# BalEv_AINb_v1_0.net
KiCad netlist of a schematic drawn in Altium Designer
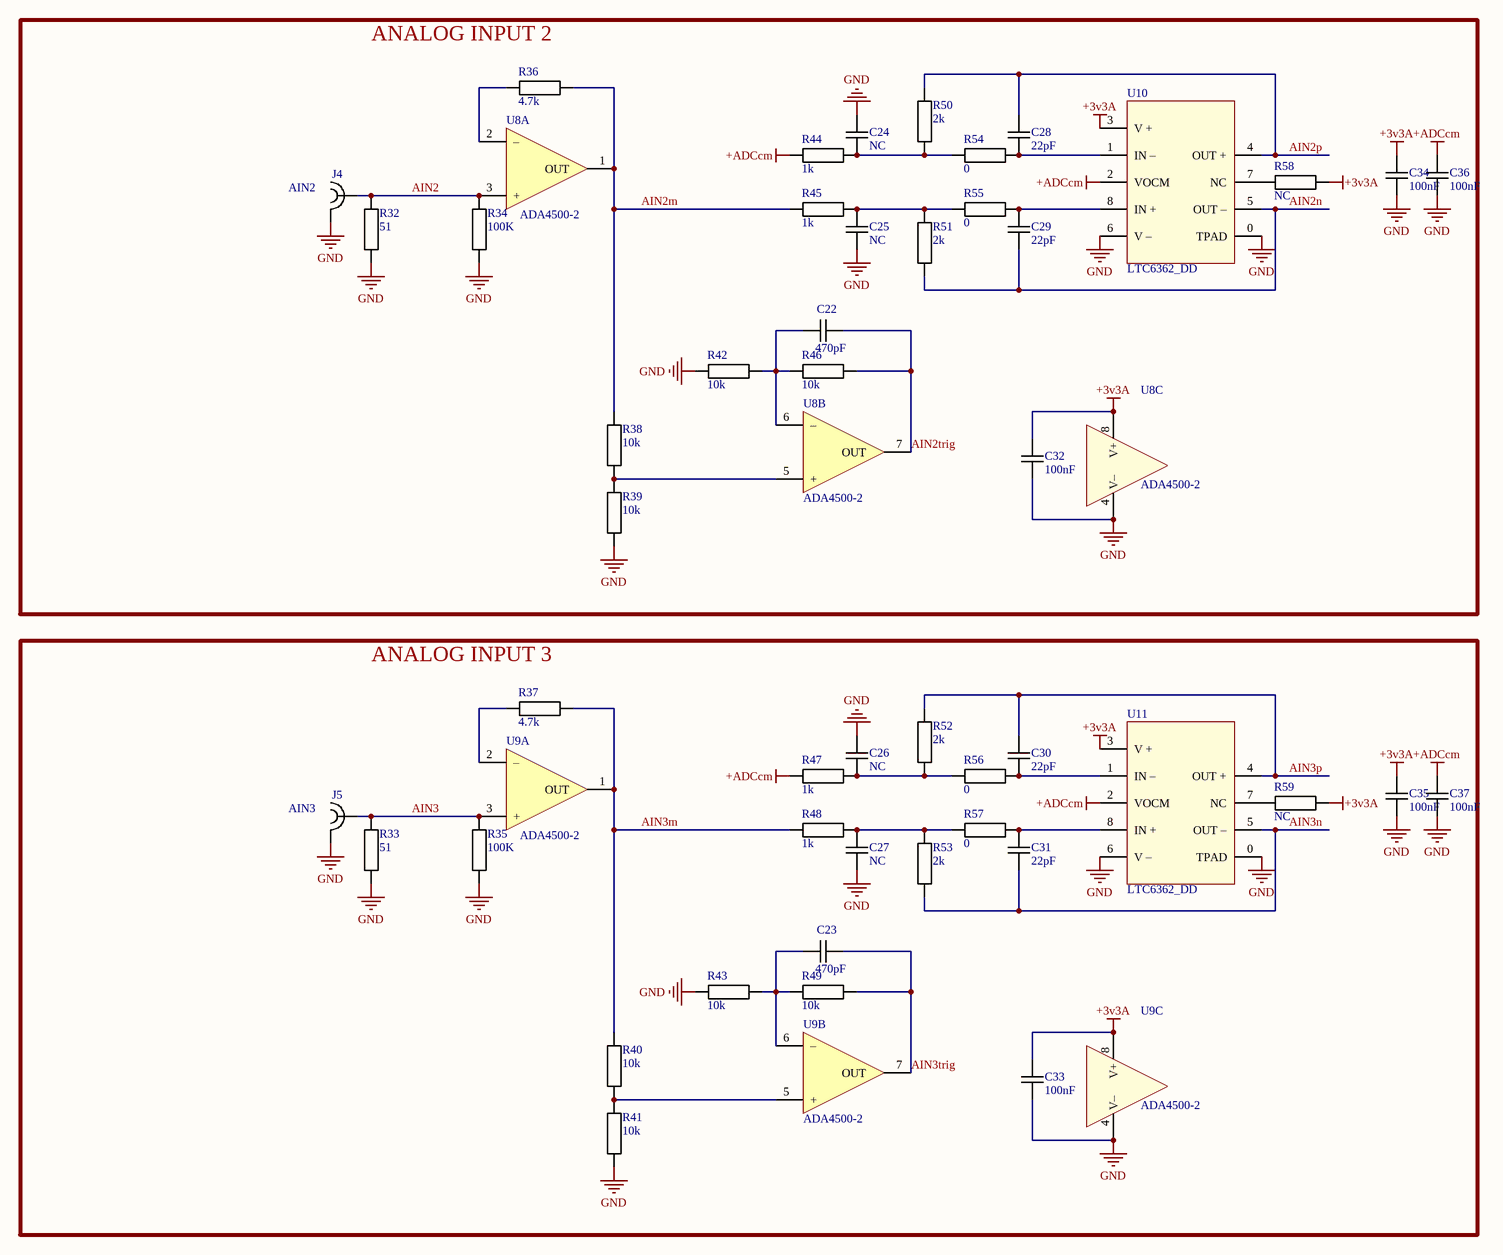
[diagram p0: BalEv_AINb_v1_0.SchDoc]

(export (version "E")
  (design (tool "Eeschema 10.0.6"))
  (components
    (comp (ref "C22")
      (value "470pF")
      (footprint "CAPACITOR 1005 REFLOW")
      (description "Capacitor")
      (libsource (lib "Capacitor") (part "Capacitor"))
    )
    (comp (ref "C23")
      (value "470pF")
      (footprint "CAPACITOR 1005 REFLOW")
      (description "Capacitor")
      (libsource (lib "Capacitor") (part "Capacitor"))
    )
    (comp (ref "C24")
      (value "NC")
      (footprint "CAPACITOR 1005 REFLOW")
      (description "Capacitor")
      (libsource (lib "Capacitor") (part "Capacitor"))
    )
    (comp (ref "C25")
      (value "NC")
      (footprint "CAPACITOR 1005 REFLOW")
      (description "Capacitor")
      (libsource (lib "Capacitor") (part "Capacitor"))
    )
    (comp (ref "C26")
      (value "NC")
      (footprint "CAPACITOR 1005 REFLOW")
      (description "Capacitor")
      (libsource (lib "Capacitor") (part "Capacitor"))
    )
    (comp (ref "C27")
      (value "NC")
      (footprint "CAPACITOR 1005 REFLOW")
      (description "Capacitor")
      (libsource (lib "Capacitor") (part "Capacitor"))
    )
    (comp (ref "C28")
      (value "22pF")
      (footprint "CAPACITOR 1005 REFLOW")
      (description "Capacitor")
      (libsource (lib "Capacitor") (part "Capacitor"))
    )
    (comp (ref "C29")
      (value "22pF")
      (footprint "CAPACITOR 1005 REFLOW")
      (description "Capacitor")
      (libsource (lib "Capacitor") (part "Capacitor"))
    )
    (comp (ref "C30")
      (value "22pF")
      (footprint "CAPACITOR 1005 REFLOW")
      (description "Capacitor")
      (libsource (lib "Capacitor") (part "Capacitor"))
    )
    (comp (ref "C31")
      (value "22pF")
      (footprint "CAPACITOR 1005 REFLOW")
      (description "Capacitor")
      (libsource (lib "Capacitor") (part "Capacitor"))
    )
    (comp (ref "C32")
      (value "100nF")
      (footprint "CAPACITOR 1005 REFLOW")
      (description "Capacitor")
      (libsource (lib "Capacitor") (part "Capacitor"))
    )
    (comp (ref "C33")
      (value "100nF")
      (footprint "CAPACITOR 1005 REFLOW")
      (description "Capacitor")
      (libsource (lib "Capacitor") (part "Capacitor"))
    )
    (comp (ref "C34")
      (value "100nF")
      (footprint "CAPACITOR 1005 REFLOW")
      (description "Capacitor")
      (libsource (lib "Capacitor") (part "Capacitor"))
    )
    (comp (ref "C35")
      (value "100nF")
      (footprint "CAPACITOR 1005 REFLOW")
      (description "Capacitor")
      (libsource (lib "Capacitor") (part "Capacitor"))
    )
    (comp (ref "C36")
      (value "100nF")
      (footprint "CAPACITOR 1005 REFLOW")
      (description "Capacitor")
      (libsource (lib "Capacitor") (part "Capacitor"))
    )
    (comp (ref "C37")
      (value "100nF")
      (footprint "CAPACITOR 1005 REFLOW")
      (description "Capacitor")
      (libsource (lib "Capacitor") (part "Capacitor"))
    )
    (comp (ref "J4")
      (value "AIN2")
      (footprint "SMA EDGE Molex 732511150")
      (description "SMA EDGE Molex 732511150")
      (libsource (lib "Connector") (part "SMA EDGE Molex 732511150"))
    )
    (comp (ref "J5")
      (value "AIN3")
      (footprint "SMA EDGE Molex 732511150")
      (description "SMA EDGE Molex 732511150")
      (libsource (lib "Connector") (part "SMA EDGE Molex 732511150"))
    )
    (comp (ref "R32")
      (value "51")
      (footprint "RESISTOR 1005 REFLOW")
      (description "Resistor")
      (libsource (lib "Resistor") (part "Resistor"))
    )
    (comp (ref "R33")
      (value "51")
      (footprint "RESISTOR 1005 REFLOW")
      (description "Resistor")
      (libsource (lib "Resistor") (part "Resistor"))
    )
    (comp (ref "R34")
      (value "100K")
      (footprint "RESISTOR 1005 REFLOW")
      (description "Resistor")
      (libsource (lib "Resistor") (part "Resistor"))
    )
    (comp (ref "R35")
      (value "100K")
      (footprint "RESISTOR 1005 REFLOW")
      (description "Resistor")
      (libsource (lib "Resistor") (part "Resistor"))
    )
    (comp (ref "R36")
      (value "4.7k")
      (footprint "RESISTOR 1005 REFLOW")
      (description "Resistor")
      (libsource (lib "Resistor") (part "Resistor"))
    )
    (comp (ref "R37")
      (value "4.7k")
      (footprint "RESISTOR 1005 REFLOW")
      (description "Resistor")
      (libsource (lib "Resistor") (part "Resistor"))
    )
    (comp (ref "R38")
      (value "10k")
      (footprint "RESISTOR 1005 REFLOW")
      (description "Resistor")
      (libsource (lib "Resistor") (part "Resistor"))
    )
    (comp (ref "R39")
      (value "10k")
      (footprint "RESISTOR 1005 REFLOW")
      (description "Resistor")
      (libsource (lib "Resistor") (part "Resistor"))
    )
    (comp (ref "R40")
      (value "10k")
      (footprint "RESISTOR 1005 REFLOW")
      (description "Resistor")
      (libsource (lib "Resistor") (part "Resistor"))
    )
    (comp (ref "R41")
      (value "10k")
      (footprint "RESISTOR 1005 REFLOW")
      (description "Resistor")
      (libsource (lib "Resistor") (part "Resistor"))
    )
    (comp (ref "R42")
      (value "10k")
      (footprint "RESISTOR 1005 REFLOW")
      (description "Resistor")
      (libsource (lib "Resistor") (part "Resistor"))
    )
    (comp (ref "R43")
      (value "10k")
      (footprint "RESISTOR 1005 REFLOW")
      (description "Resistor")
      (libsource (lib "Resistor") (part "Resistor"))
    )
    (comp (ref "R44")
      (value "1k")
      (footprint "RESISTOR 1005 REFLOW")
      (description "Resistor")
      (libsource (lib "Resistor") (part "Resistor"))
    )
    (comp (ref "R45")
      (value "1k")
      (footprint "RESISTOR 1005 REFLOW")
      (description "Resistor")
      (libsource (lib "Resistor") (part "Resistor"))
    )
    (comp (ref "R46")
      (value "10k")
      (footprint "RESISTOR 1005 REFLOW")
      (description "Resistor")
      (libsource (lib "Resistor") (part "Resistor"))
    )
    (comp (ref "R47")
      (value "1k")
      (footprint "RESISTOR 1005 REFLOW")
      (description "Resistor")
      (libsource (lib "Resistor") (part "Resistor"))
    )
    (comp (ref "R48")
      (value "1k")
      (footprint "RESISTOR 1005 REFLOW")
      (description "Resistor")
      (libsource (lib "Resistor") (part "Resistor"))
    )
    (comp (ref "R49")
      (value "10k")
      (footprint "RESISTOR 1005 REFLOW")
      (description "Resistor")
      (libsource (lib "Resistor") (part "Resistor"))
    )
    (comp (ref "R50")
      (value "2k")
      (footprint "RESISTOR 1005 REFLOW")
      (description "Resistor")
      (libsource (lib "Resistor") (part "Resistor"))
    )
    (comp (ref "R51")
      (value "2k")
      (footprint "RESISTOR 1005 REFLOW")
      (description "Resistor")
      (libsource (lib "Resistor") (part "Resistor"))
    )
    (comp (ref "R52")
      (value "2k")
      (footprint "RESISTOR 1005 REFLOW")
      (description "Resistor")
      (libsource (lib "Resistor") (part "Resistor"))
    )
    (comp (ref "R53")
      (value "2k")
      (footprint "RESISTOR 1005 REFLOW")
      (description "Resistor")
      (libsource (lib "Resistor") (part "Resistor"))
    )
    (comp (ref "R54")
      (value "0")
      (footprint "RESISTOR 1005 REFLOW")
      (description "Resistor")
      (libsource (lib "Resistor") (part "Resistor"))
    )
    (comp (ref "R55")
      (value "0")
      (footprint "RESISTOR 1005 REFLOW")
      (description "Resistor")
      (libsource (lib "Resistor") (part "Resistor"))
    )
    (comp (ref "R56")
      (value "0")
      (footprint "RESISTOR 1005 REFLOW")
      (description "Resistor")
      (libsource (lib "Resistor") (part "Resistor"))
    )
    (comp (ref "R57")
      (value "0")
      (footprint "RESISTOR 1005 REFLOW")
      (description "Resistor")
      (libsource (lib "Resistor") (part "Resistor"))
    )
    (comp (ref "R58")
      (value "NC")
      (footprint "RESISTOR 1005 REFLOW")
      (description "Resistor")
      (libsource (lib "Resistor") (part "Resistor"))
    )
    (comp (ref "R59")
      (value "NC")
      (footprint "RESISTOR 1005 REFLOW")
      (description "Resistor")
      (libsource (lib "Resistor") (part "Resistor"))
    )
    (comp (ref "U8")
      (value "ADA4500-2")
      (footprint "MSOP8 P0.65 C3.0X3.0 H1.1")
      (description "Generic dual OPA 8 pins")
      (libsource (lib "Amplifier") (part "OPA DUAL"))
    )
    (comp (ref "U9")
      (value "ADA4500-2")
      (footprint "MSOP8 P0.65 C3.0X3.0 H1.1")
      (description "Generic dual OPA 8 pins")
      (libsource (lib "Amplifier") (part "OPA DUAL"))
    )
    (comp (ref "U10")
      (value "LTC6362_DD")
      (footprint "LFCSP8 P0.5 C3.0x2.8 H1.0")
      (description "IC OPAMP DIFF 410MHZ RRO 8LFCSP")
      (libsource (lib "Amplifier") (part "AD8139ACP"))
    )
    (comp (ref "U11")
      (value "LTC6362_DD")
      (footprint "LFCSP8 P0.5 C3.0x2.8 H1.0")
      (description "IC OPAMP DIFF 410MHZ RRO 8LFCSP")
      (libsource (lib "Amplifier") (part "AD8139ACP"))
    )
  )
  (nets
    (net (code "1") (name "+3v3A") (class "Default")
      (node (ref "C32") (pin "1") (pinfunction "1_1") (pintype "passive"))
      (node (ref "C33") (pin "1") (pinfunction "1_1") (pintype "passive"))
      (node (ref "C34") (pin "2") (pinfunction "2_2") (pintype "passive"))
      (node (ref "C35") (pin "2") (pinfunction "2_2") (pintype "passive"))
      (node (ref "R58") (pin "2") (pinfunction "2_2") (pintype "passive"))
      (node (ref "R59") (pin "2") (pinfunction "2_2") (pintype "passive"))
      (node (ref "U10") (pin "3") (pinfunction "V_+_3") (pintype "passive"))
      (node (ref "U11") (pin "3") (pinfunction "V_+_3") (pintype "passive"))
      (node (ref "U8") (pin "8") (pinfunction "V+_8") (pintype "passive"))
      (node (ref "U9") (pin "8") (pinfunction "V+_8") (pintype "passive"))
    )
    (net (code "2") (name "+ADCcm") (class "Default")
      (node (ref "C36") (pin "2") (pinfunction "2_2") (pintype "passive"))
      (node (ref "C37") (pin "2") (pinfunction "2_2") (pintype "passive"))
      (node (ref "R44") (pin "1") (pinfunction "1_1") (pintype "passive"))
      (node (ref "R47") (pin "1") (pinfunction "1_1") (pintype "passive"))
      (node (ref "U10") (pin "2") (pinfunction "VOCM_2") (pintype "passive"))
      (node (ref "U11") (pin "2") (pinfunction "VOCM_2") (pintype "passive"))
    )
    (net (code "3") (name "/AIN2") (class "Default")
      (node (ref "J4") (pin "1") (pinfunction "1_1") (pintype "passive"))
      (node (ref "R32") (pin "2") (pinfunction "2_2") (pintype "passive"))
      (node (ref "R34") (pin "2") (pinfunction "2_2") (pintype "passive"))
      (node (ref "U8") (pin "3") (pinfunction "+_3") (pintype "passive"))
    )
    (net (code "4") (name "/AIN2m") (class "Default")
      (node (ref "R36") (pin "2") (pinfunction "2_2") (pintype "passive"))
      (node (ref "R38") (pin "1") (pinfunction "1_1") (pintype "passive"))
      (node (ref "R45") (pin "1") (pinfunction "1_1") (pintype "passive"))
      (node (ref "U8") (pin "1") (pinfunction "OUT_1") (pintype "passive"))
    )
    (net (code "5") (name "/AIN2n") (class "Default")
      (node (ref "C29") (pin "1") (pinfunction "1_1") (pintype "passive"))
      (node (ref "R51") (pin "2") (pinfunction "2_2") (pintype "passive"))
      (node (ref "U10") (pin "5") (pinfunction "OUT_–_5") (pintype "passive"))
    )
    (net (code "6") (name "/AIN2p") (class "Default")
      (node (ref "C28") (pin "1") (pinfunction "1_1") (pintype "passive"))
      (node (ref "R50") (pin "2") (pinfunction "2_2") (pintype "passive"))
      (node (ref "U10") (pin "4") (pinfunction "OUT_+_4") (pintype "passive"))
    )
    (net (code "7") (name "/AIN2trig") (class "Default")
      (node (ref "C22") (pin "1") (pinfunction "1_1") (pintype "passive"))
      (node (ref "R46") (pin "2") (pinfunction "2_2") (pintype "passive"))
      (node (ref "U8") (pin "7") (pinfunction "OUT_7") (pintype "passive"))
    )
    (net (code "8") (name "/AIN3") (class "Default")
      (node (ref "J5") (pin "1") (pinfunction "1_1") (pintype "passive"))
      (node (ref "R33") (pin "2") (pinfunction "2_2") (pintype "passive"))
      (node (ref "R35") (pin "2") (pinfunction "2_2") (pintype "passive"))
      (node (ref "U9") (pin "3") (pinfunction "+_3") (pintype "passive"))
    )
    (net (code "9") (name "/AIN3m") (class "Default")
      (node (ref "R37") (pin "2") (pinfunction "2_2") (pintype "passive"))
      (node (ref "R40") (pin "1") (pinfunction "1_1") (pintype "passive"))
      (node (ref "R48") (pin "1") (pinfunction "1_1") (pintype "passive"))
      (node (ref "U9") (pin "1") (pinfunction "OUT_1") (pintype "passive"))
    )
    (net (code "10") (name "/AIN3n") (class "Default")
      (node (ref "C31") (pin "1") (pinfunction "1_1") (pintype "passive"))
      (node (ref "R53") (pin "2") (pinfunction "2_2") (pintype "passive"))
      (node (ref "U11") (pin "5") (pinfunction "OUT_–_5") (pintype "passive"))
    )
    (net (code "11") (name "/AIN3p") (class "Default")
      (node (ref "C30") (pin "1") (pinfunction "1_1") (pintype "passive"))
      (node (ref "R52") (pin "2") (pinfunction "2_2") (pintype "passive"))
      (node (ref "U11") (pin "4") (pinfunction "OUT_+_4") (pintype "passive"))
    )
    (net (code "12") (name "/AIN3trig") (class "Default")
      (node (ref "C23") (pin "1") (pinfunction "1_1") (pintype "passive"))
      (node (ref "R49") (pin "2") (pinfunction "2_2") (pintype "passive"))
      (node (ref "U9") (pin "7") (pinfunction "OUT_7") (pintype "passive"))
    )
    (net (code "13") (name "GND") (class "Default")
      (node (ref "C24") (pin "1") (pinfunction "1_1") (pintype "passive"))
      (node (ref "C25") (pin "2") (pinfunction "2_2") (pintype "passive"))
      (node (ref "C26") (pin "1") (pinfunction "1_1") (pintype "passive"))
      (node (ref "C27") (pin "2") (pinfunction "2_2") (pintype "passive"))
      (node (ref "C32") (pin "2") (pinfunction "2_2") (pintype "passive"))
      (node (ref "C33") (pin "2") (pinfunction "2_2") (pintype "passive"))
      (node (ref "C34") (pin "1") (pinfunction "1_1") (pintype "passive"))
      (node (ref "C35") (pin "1") (pinfunction "1_1") (pintype "passive"))
      (node (ref "C36") (pin "1") (pinfunction "1_1") (pintype "passive"))
      (node (ref "C37") (pin "1") (pinfunction "1_1") (pintype "passive"))
      (node (ref "J4") (pin "2") (pinfunction "2_2") (pintype "passive"))
      (node (ref "J5") (pin "2") (pinfunction "2_2") (pintype "passive"))
      (node (ref "R32") (pin "1") (pinfunction "1_1") (pintype "passive"))
      (node (ref "R33") (pin "1") (pinfunction "1_1") (pintype "passive"))
      (node (ref "R34") (pin "1") (pinfunction "1_1") (pintype "passive"))
      (node (ref "R35") (pin "1") (pinfunction "1_1") (pintype "passive"))
      (node (ref "R39") (pin "2") (pinfunction "2_2") (pintype "passive"))
      (node (ref "R41") (pin "2") (pinfunction "2_2") (pintype "passive"))
      (node (ref "R42") (pin "1") (pinfunction "1_1") (pintype "passive"))
      (node (ref "R43") (pin "1") (pinfunction "1_1") (pintype "passive"))
      (node (ref "U10") (pin "0") (pinfunction "TPAD_0") (pintype "passive"))
      (node (ref "U10") (pin "6") (pinfunction "V_–_6") (pintype "passive"))
      (node (ref "U11") (pin "0") (pinfunction "TPAD_0") (pintype "passive"))
      (node (ref "U11") (pin "6") (pinfunction "V_–_6") (pintype "passive"))
      (node (ref "U8") (pin "4") (pinfunction "V–_4") (pintype "passive"))
      (node (ref "U9") (pin "4") (pinfunction "V–_4") (pintype "passive"))
    )
    (net (code "14") (name "Net-(C24-Pad2)") (class "Default")
      (node (ref "C24") (pin "2") (pinfunction "2_2") (pintype "passive"))
      (node (ref "R44") (pin "2") (pinfunction "2_2") (pintype "passive"))
      (node (ref "R50") (pin "1") (pinfunction "1_1") (pintype "passive"))
      (node (ref "R54") (pin "2") (pinfunction "2_2") (pintype "passive"))
    )
    (net (code "15") (name "Net-(C25-Pad1)") (class "Default")
      (node (ref "C25") (pin "1") (pinfunction "1_1") (pintype "passive"))
      (node (ref "R45") (pin "2") (pinfunction "2_2") (pintype "passive"))
      (node (ref "R51") (pin "1") (pinfunction "1_1") (pintype "passive"))
      (node (ref "R55") (pin "1") (pinfunction "1_1") (pintype "passive"))
    )
    (net (code "16") (name "Net-(C26-Pad2)") (class "Default")
      (node (ref "C26") (pin "2") (pinfunction "2_2") (pintype "passive"))
      (node (ref "R47") (pin "2") (pinfunction "2_2") (pintype "passive"))
      (node (ref "R52") (pin "1") (pinfunction "1_1") (pintype "passive"))
      (node (ref "R56") (pin "2") (pinfunction "2_2") (pintype "passive"))
    )
    (net (code "17") (name "Net-(C27-Pad1)") (class "Default")
      (node (ref "C27") (pin "1") (pinfunction "1_1") (pintype "passive"))
      (node (ref "R48") (pin "2") (pinfunction "2_2") (pintype "passive"))
      (node (ref "R53") (pin "1") (pinfunction "1_1") (pintype "passive"))
      (node (ref "R57") (pin "1") (pinfunction "1_1") (pintype "passive"))
    )
    (net (code "18") (name "Net-(U8A-–)") (class "Default")
      (node (ref "R36") (pin "1") (pinfunction "1_1") (pintype "passive"))
      (node (ref "U8") (pin "2") (pinfunction "–_2") (pintype "passive"))
    )
    (net (code "19") (name "Net-(U8B-+)") (class "Default")
      (node (ref "R38") (pin "2") (pinfunction "2_2") (pintype "passive"))
      (node (ref "R39") (pin "1") (pinfunction "1_1") (pintype "passive"))
      (node (ref "U8") (pin "5") (pinfunction "+_5") (pintype "passive"))
    )
    (net (code "20") (name "Net-(U8B-–)") (class "Default")
      (node (ref "C22") (pin "2") (pinfunction "2_2") (pintype "passive"))
      (node (ref "R42") (pin "2") (pinfunction "2_2") (pintype "passive"))
      (node (ref "R46") (pin "1") (pinfunction "1_1") (pintype "passive"))
      (node (ref "U8") (pin "6") (pinfunction "–_6") (pintype "passive"))
    )
    (net (code "21") (name "Net-(U9A-–)") (class "Default")
      (node (ref "R37") (pin "1") (pinfunction "1_1") (pintype "passive"))
      (node (ref "U9") (pin "2") (pinfunction "–_2") (pintype "passive"))
    )
    (net (code "22") (name "Net-(U9B-+)") (class "Default")
      (node (ref "R40") (pin "2") (pinfunction "2_2") (pintype "passive"))
      (node (ref "R41") (pin "1") (pinfunction "1_1") (pintype "passive"))
      (node (ref "U9") (pin "5") (pinfunction "+_5") (pintype "passive"))
    )
    (net (code "23") (name "Net-(U9B-–)") (class "Default")
      (node (ref "C23") (pin "2") (pinfunction "2_2") (pintype "passive"))
      (node (ref "R43") (pin "2") (pinfunction "2_2") (pintype "passive"))
      (node (ref "R49") (pin "1") (pinfunction "1_1") (pintype "passive"))
      (node (ref "U9") (pin "6") (pinfunction "–_6") (pintype "passive"))
    )
    (net (code "24") (name "Net-(U10-IN_+)") (class "Default")
      (node (ref "C29") (pin "2") (pinfunction "2_2") (pintype "passive"))
      (node (ref "R55") (pin "2") (pinfunction "2_2") (pintype "passive"))
      (node (ref "U10") (pin "8") (pinfunction "IN_+_8") (pintype "passive"))
    )
    (net (code "25") (name "Net-(U10-IN_–)") (class "Default")
      (node (ref "C28") (pin "2") (pinfunction "2_2") (pintype "passive"))
      (node (ref "R54") (pin "1") (pinfunction "1_1") (pintype "passive"))
      (node (ref "U10") (pin "1") (pinfunction "IN_–_1") (pintype "passive"))
    )
    (net (code "26") (name "Net-(U10-NC)") (class "Default")
      (node (ref "R58") (pin "1") (pinfunction "1_1") (pintype "passive"))
      (node (ref "U10") (pin "7") (pinfunction "NC_7") (pintype "passive"))
    )
    (net (code "27") (name "Net-(U11-IN_+)") (class "Default")
      (node (ref "C31") (pin "2") (pinfunction "2_2") (pintype "passive"))
      (node (ref "R57") (pin "2") (pinfunction "2_2") (pintype "passive"))
      (node (ref "U11") (pin "8") (pinfunction "IN_+_8") (pintype "passive"))
    )
    (net (code "28") (name "Net-(U11-IN_–)") (class "Default")
      (node (ref "C30") (pin "2") (pinfunction "2_2") (pintype "passive"))
      (node (ref "R56") (pin "1") (pinfunction "1_1") (pintype "passive"))
      (node (ref "U11") (pin "1") (pinfunction "IN_–_1") (pintype "passive"))
    )
    (net (code "29") (name "Net-(U11-NC)") (class "Default")
      (node (ref "R59") (pin "1") (pinfunction "1_1") (pintype "passive"))
      (node (ref "U11") (pin "7") (pinfunction "NC_7") (pintype "passive"))
    )
  )
)
